# romano16f628.net
KiCad netlist of a schematic drawn in EAGLE
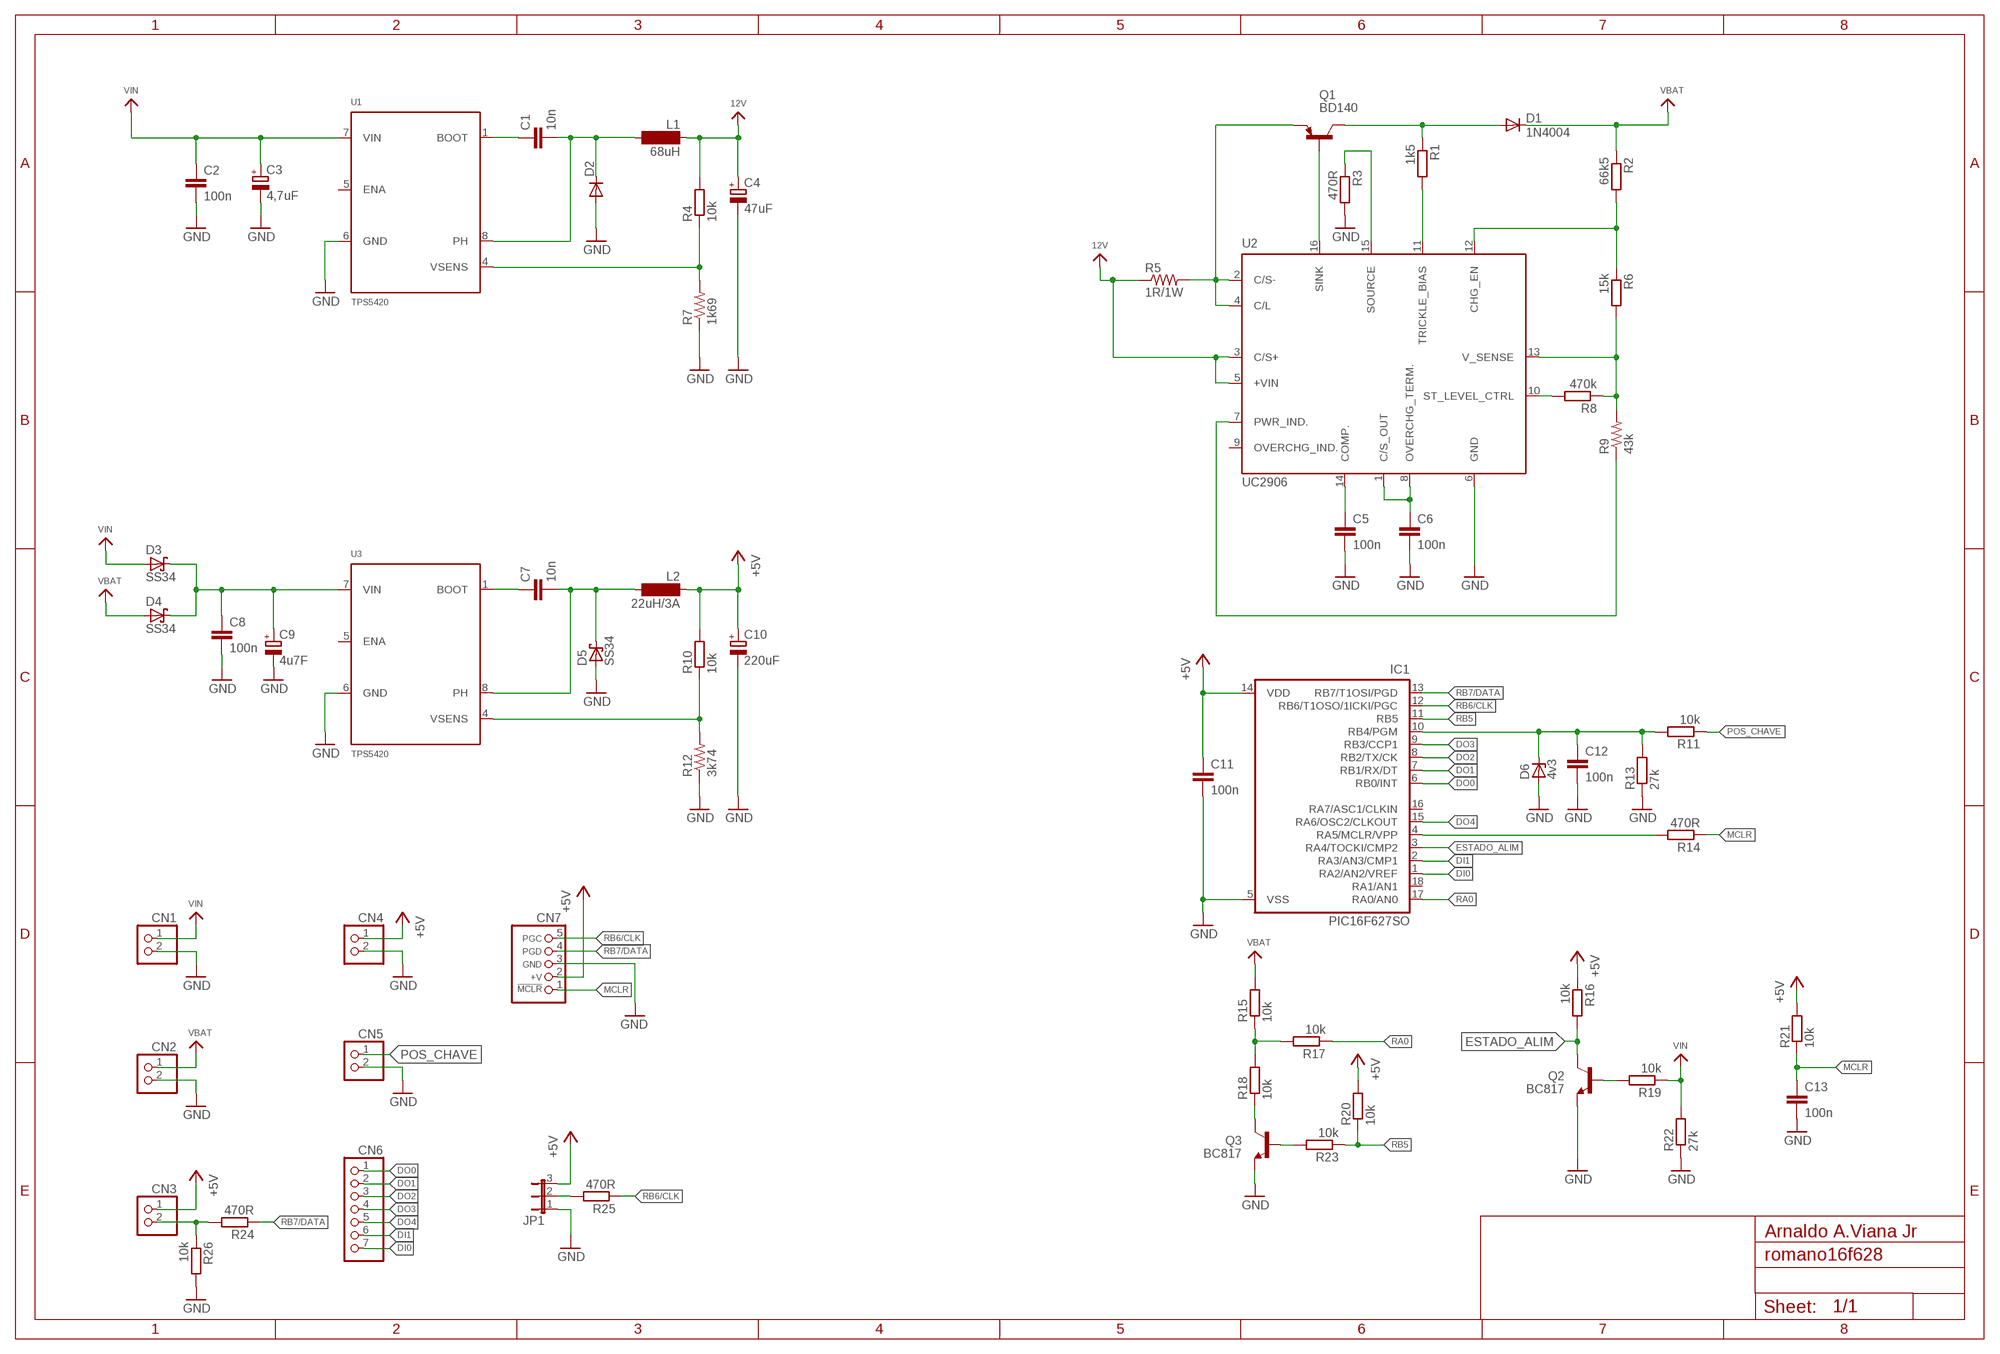
[diagram p0: schematic, sheet 1]

(export (version "E")
  (design (tool "Eeschema 10.0.6"))
  (components
    (comp (ref "C1")
      (value "10n")
      (footprint "eagle-import:C0805")
      (libsource (lib "eagle-import") (part "C-EUC0805"))
    )
    (comp (ref "C2")
      (value "100n")
      (footprint "eagle-import:C0805")
      (libsource (lib "eagle-import") (part "C-EUC0805"))
    )
    (comp (ref "C3")
      (value "4,7uF")
      (footprint "eagle-import:E5-6")
      (libsource (lib "eagle-import") (part "CPOL-EUE5-6"))
    )
    (comp (ref "C4")
      (value "47uF")
      (footprint "eagle-import:E5-6")
      (libsource (lib "eagle-import") (part "CPOL-EUE5-6"))
    )
    (comp (ref "C5")
      (value "100n")
      (footprint "eagle-import:C0805")
      (libsource (lib "eagle-import") (part "C-EUC0805"))
    )
    (comp (ref "C6")
      (value "100n")
      (footprint "eagle-import:C0805")
      (libsource (lib "eagle-import") (part "C-EUC0805"))
    )
    (comp (ref "C7")
      (value "10n")
      (footprint "eagle-import:C0805")
      (libsource (lib "eagle-import") (part "C-EUC0805"))
    )
    (comp (ref "C8")
      (value "100n")
      (footprint "eagle-import:C0805")
      (libsource (lib "eagle-import") (part "C-EUC0805"))
    )
    (comp (ref "C9")
      (value "4u7F")
      (footprint "eagle-import:E5-6")
      (libsource (lib "eagle-import") (part "CPOL-EUE5-6"))
    )
    (comp (ref "C10")
      (value "220uF")
      (footprint "eagle-import:E5-6")
      (libsource (lib "eagle-import") (part "CPOL-EUE5-6"))
    )
    (comp (ref "C11")
      (value "100n")
      (footprint "eagle-import:C0805")
      (libsource (lib "eagle-import") (part "C-EUC0805"))
    )
    (comp (ref "C12")
      (value "100n")
      (footprint "eagle-import:C0805")
      (libsource (lib "eagle-import") (part "C-EUC0805"))
    )
    (comp (ref "C13")
      (value "100n")
      (footprint "eagle-import:C0805")
      (libsource (lib "eagle-import") (part "C-EUC0805"))
    )
    (comp (ref "CN1")
      (value "HEADER-1X2ROUND")
      (footprint "eagle-import:1X02_ROUND")
      (libsource (lib "eagle-import") (part "HEADER-1X2ROUND"))
    )
    (comp (ref "CN2")
      (value "HEADER-1X2ROUND")
      (footprint "eagle-import:1X02_ROUND")
      (libsource (lib "eagle-import") (part "HEADER-1X2ROUND"))
    )
    (comp (ref "CN3")
      (value "HEADER-1X2ROUND")
      (footprint "eagle-import:1X02_ROUND")
      (libsource (lib "eagle-import") (part "HEADER-1X2ROUND"))
    )
    (comp (ref "CN4")
      (value "HEADER-1X2ROUND")
      (footprint "eagle-import:1X02_ROUND")
      (libsource (lib "eagle-import") (part "HEADER-1X2ROUND"))
    )
    (comp (ref "CN5")
      (value "HEADER-1X2ROUND")
      (footprint "eagle-import:1X02_ROUND")
      (libsource (lib "eagle-import") (part "HEADER-1X2ROUND"))
    )
    (comp (ref "CN6")
      (value "HEADER-1X7ROUND")
      (footprint "eagle-import:1X07_ROUND")
      (libsource (lib "eagle-import") (part "HEADER-1X7ROUND"))
    )
    (comp (ref "CN7")
      (value "CON_HEADER_PRG_PIC_ICSP0.1INCH_A")
      (footprint "eagle-import:HEADER_PRG_1X05")
      (libsource (lib "eagle-import") (part "CON_HEADER_PRG_PIC_ICSP0.1INCH_A"))
    )
    (comp (ref "D1")
      (value "1N4004")
      (footprint "eagle-import:DO41-10")
      (libsource (lib "eagle-import") (part "1N4004"))
    )
    (comp (ref "D2")
      (value "DIODE-SOD123")
      (footprint "eagle-import:SOD123")
      (libsource (lib "eagle-import") (part "DIODE-SOD123"))
    )
    (comp (ref "D3")
      (value "SS34")
      (footprint "eagle-import:SMC")
      (libsource (lib "eagle-import") (part "SCHOTTKY-DIODESMC"))
    )
    (comp (ref "D4")
      (value "SS34")
      (footprint "eagle-import:SMC")
      (libsource (lib "eagle-import") (part "SCHOTTKY-DIODESMC"))
    )
    (comp (ref "D5")
      (value "SS34")
      (footprint "eagle-import:SMC")
      (libsource (lib "eagle-import") (part "SCHOTTKY-DIODESMC"))
    )
    (comp (ref "D6")
      (value "4v3")
      (footprint "eagle-import:SOT23")
      (libsource (lib "eagle-import") (part "ZENER-DIODESOT23"))
    )
    (comp (ref "IC1")
      (value "PIC16F627SO")
      (footprint "eagle-import:SO-18W")
      (fields
        (field (name "MF") "MICROCHIP")
        (field (name "MPN") "PIC16F627-04/SO")
        (field (name "MPN_1") "PIC16F627-04/SO")
        (field (name "OC_FARNELL") "1084265")
        (field (name "OC_NEWARK") "69K7632")
      )
      (libsource (lib "eagle-import") (part "PIC16F627SO"))
    )
    (comp (ref "JP1")
      (value "JUMPER3")
      (footprint "eagle-import:JUMPER3")
      (libsource (lib "eagle-import") (part "JUMPER3"))
    )
    (comp (ref "L1")
      (value "68uH")
      (footprint "eagle-import:SD12K100")
      (libsource (lib "eagle-import") (part "SD12K100"))
    )
    (comp (ref "L2")
      (value "22uH/3A")
      (footprint "eagle-import:SD12K100")
      (libsource (lib "eagle-import") (part "SD12K100"))
    )
    (comp (ref "Q1")
      (value "BD140")
      (footprint "eagle-import:TO126")
      (libsource (lib "eagle-import") (part "BD140"))
    )
    (comp (ref "Q2")
      (value "BC817")
      (footprint "eagle-import:SOT23-BEC")
      (libsource (lib "eagle-import") (part "-NPN-SOT23-BECBC817-16"))
    )
    (comp (ref "Q3")
      (value "BC817")
      (footprint "eagle-import:SOT23-BEC")
      (libsource (lib "eagle-import") (part "-NPN-SOT23-BECBC817-16"))
    )
    (comp (ref "R1")
      (value "1k5")
      (footprint "eagle-import:R0805")
      (libsource (lib "eagle-import") (part "R-EU_R0805"))
    )
    (comp (ref "R2")
      (value "66k5")
      (footprint "eagle-import:R0805")
      (libsource (lib "eagle-import") (part "R-EU_R0805"))
    )
    (comp (ref "R3")
      (value "470R")
      (footprint "eagle-import:R0805")
      (libsource (lib "eagle-import") (part "R-EU_R0805"))
    )
    (comp (ref "R4")
      (value "10k")
      (footprint "eagle-import:R0805")
      (libsource (lib "eagle-import") (part "R-EU_R0805"))
    )
    (comp (ref "R5")
      (value "1R/1W")
      (footprint "eagle-import:0805-THM")
      (libsource (lib "eagle-import") (part "RESISTOR_DUAL"))
    )
    (comp (ref "R6")
      (value "15k")
      (footprint "eagle-import:R0805")
      (libsource (lib "eagle-import") (part "R-EU_R0805"))
    )
    (comp (ref "R7")
      (value "1k69")
      (footprint "eagle-import:0805-THM")
      (libsource (lib "eagle-import") (part "RESISTOR_DUAL"))
    )
    (comp (ref "R8")
      (value "470k")
      (footprint "eagle-import:R0805")
      (libsource (lib "eagle-import") (part "R-EU_R0805"))
    )
    (comp (ref "R9")
      (value "43k")
      (footprint "eagle-import:0805-THM")
      (libsource (lib "eagle-import") (part "RESISTOR_DUAL"))
    )
    (comp (ref "R10")
      (value "10k")
      (footprint "eagle-import:R0805")
      (libsource (lib "eagle-import") (part "R-EU_R0805"))
    )
    (comp (ref "R11")
      (value "10k")
      (footprint "eagle-import:R0805")
      (libsource (lib "eagle-import") (part "R-EU_R0805"))
    )
    (comp (ref "R12")
      (value "3k74")
      (footprint "eagle-import:0805-THM")
      (libsource (lib "eagle-import") (part "RESISTOR_DUAL"))
    )
    (comp (ref "R13")
      (value "27k")
      (footprint "eagle-import:R0805")
      (libsource (lib "eagle-import") (part "R-EU_R0805"))
    )
    (comp (ref "R14")
      (value "470R")
      (footprint "eagle-import:R0805")
      (libsource (lib "eagle-import") (part "R-EU_R0805"))
    )
    (comp (ref "R15")
      (value "10k")
      (footprint "eagle-import:R0805")
      (libsource (lib "eagle-import") (part "R-EU_R0805"))
    )
    (comp (ref "R16")
      (value "10k")
      (footprint "eagle-import:R0805")
      (libsource (lib "eagle-import") (part "R-EU_R0805"))
    )
    (comp (ref "R17")
      (value "10k")
      (footprint "eagle-import:R0805")
      (libsource (lib "eagle-import") (part "R-EU_R0805"))
    )
    (comp (ref "R18")
      (value "10k")
      (footprint "eagle-import:R0805")
      (libsource (lib "eagle-import") (part "R-EU_R0805"))
    )
    (comp (ref "R19")
      (value "10k")
      (footprint "eagle-import:R0805")
      (libsource (lib "eagle-import") (part "R-EU_R0805"))
    )
    (comp (ref "R20")
      (value "10k")
      (footprint "eagle-import:R0805")
      (libsource (lib "eagle-import") (part "R-EU_R0805"))
    )
    (comp (ref "R21")
      (value "10k")
      (footprint "eagle-import:R0805")
      (libsource (lib "eagle-import") (part "R-EU_R0805"))
    )
    (comp (ref "R22")
      (value "27k")
      (footprint "eagle-import:R0805")
      (libsource (lib "eagle-import") (part "R-EU_R0805"))
    )
    (comp (ref "R23")
      (value "10k")
      (footprint "eagle-import:R0805")
      (libsource (lib "eagle-import") (part "R-EU_R0805"))
    )
    (comp (ref "R24")
      (value "470R")
      (footprint "eagle-import:R0805")
      (libsource (lib "eagle-import") (part "R-EU_R0805"))
    )
    (comp (ref "R25")
      (value "470R")
      (footprint "eagle-import:R0805")
      (libsource (lib "eagle-import") (part "R-EU_R0805"))
    )
    (comp (ref "R26")
      (value "10k")
      (footprint "eagle-import:R0805")
      (libsource (lib "eagle-import") (part "R-EU_R0805"))
    )
    (comp (ref "U1")
      (value "TPS5420")
      (footprint "eagle-import:SOIC8_150MIL")
      (libsource (lib "eagle-import") (part "TPS5420"))
    )
    (comp (ref "U2")
      (value "UC2906")
      (footprint "eagle-import:SOIC_16")
      (libsource (lib "eagle-import") (part "UC2906"))
    )
    (comp (ref "U3")
      (value "TPS5420")
      (footprint "eagle-import:SOIC8_150MIL")
      (libsource (lib "eagle-import") (part "TPS5420"))
    )
  )
  (nets
    (net (code "1") (name "+5V") (class "Default")
      (node (ref "C10") (pin "+") (pinfunction "+_+") (pintype "passive"))
      (node (ref "C11") (pin "1") (pinfunction "1_1") (pintype "passive"))
      (node (ref "CN3") (pin "1") (pinfunction "1_1") (pintype "passive"))
      (node (ref "CN4") (pin "1") (pinfunction "1_1") (pintype "passive"))
      (node (ref "CN7") (pin "2") (pinfunction "+V_2") (pintype "passive"))
      (node (ref "IC1") (pin "14") (pinfunction "VDD_14") (pintype "power_in"))
      (node (ref "JP1") (pin "3") (pinfunction "3_3") (pintype "passive"))
      (node (ref "L2") (pin "1") (pinfunction "1_1") (pintype "passive"))
      (node (ref "R10") (pin "2") (pinfunction "2_2") (pintype "passive"))
      (node (ref "R16") (pin "1") (pinfunction "1_1") (pintype "passive"))
      (node (ref "R20") (pin "2") (pinfunction "2_2") (pintype "passive"))
      (node (ref "R21") (pin "2") (pinfunction "2_2") (pintype "passive"))
    )
    (net (code "2") (name "12V") (class "Default")
      (node (ref "C4") (pin "+") (pinfunction "+_+") (pintype "passive"))
      (node (ref "L1") (pin "1") (pinfunction "1_1") (pintype "passive"))
      (node (ref "R4") (pin "2") (pinfunction "2_2") (pintype "passive"))
      (node (ref "R5") (pin "1") (pinfunction "1_1") (pintype "passive"))
      (node (ref "U2") (pin "3") (pinfunction "C/S+_3") (pintype "bidirectional"))
      (node (ref "U2") (pin "5") (pinfunction "+VIN_5") (pintype "bidirectional"))
    )
    (net (code "3") (name "DI0") (class "Default")
      (node (ref "CN6") (pin "7") (pinfunction "7_7") (pintype "passive"))
      (node (ref "IC1") (pin "1") (pinfunction "RA2/AN2/VREF_1") (pintype "bidirectional"))
    )
    (net (code "4") (name "DI1") (class "Default")
      (node (ref "CN6") (pin "6") (pinfunction "6_6") (pintype "passive"))
      (node (ref "IC1") (pin "2") (pinfunction "RA3/AN3/CMP1_2") (pintype "bidirectional"))
    )
    (net (code "5") (name "DO0") (class "Default")
      (node (ref "CN6") (pin "1") (pinfunction "1_1") (pintype "passive"))
      (node (ref "IC1") (pin "6") (pinfunction "RB0/INT_6") (pintype "bidirectional"))
    )
    (net (code "6") (name "DO1") (class "Default")
      (node (ref "CN6") (pin "2") (pinfunction "2_2") (pintype "passive"))
      (node (ref "IC1") (pin "7") (pinfunction "RB1/RX/DT_7") (pintype "bidirectional"))
    )
    (net (code "7") (name "DO2") (class "Default")
      (node (ref "CN6") (pin "3") (pinfunction "3_3") (pintype "passive"))
      (node (ref "IC1") (pin "8") (pinfunction "RB2/TX/CK_8") (pintype "bidirectional"))
    )
    (net (code "8") (name "DO3") (class "Default")
      (node (ref "CN6") (pin "4") (pinfunction "4_4") (pintype "passive"))
      (node (ref "IC1") (pin "9") (pinfunction "RB3/CCP1_9") (pintype "bidirectional"))
    )
    (net (code "9") (name "DO4") (class "Default")
      (node (ref "CN6") (pin "5") (pinfunction "5_5") (pintype "passive"))
      (node (ref "IC1") (pin "15") (pinfunction "RA6/OSC2/CLKOUT_15") (pintype "bidirectional"))
    )
    (net (code "10") (name "ESTADO_ALIM") (class "Default")
      (node (ref "IC1") (pin "3") (pinfunction "RA4/TOCKI/CMP2_3") (pintype "bidirectional"))
      (node (ref "Q2") (pin "C") (pinfunction "C_C") (pintype "passive"))
      (node (ref "R16") (pin "2") (pinfunction "2_2") (pintype "passive"))
    )
    (net (code "11") (name "GND") (class "Default")
      (node (ref "C10") (pin "-") (pinfunction "-_-") (pintype "passive"))
      (node (ref "C11") (pin "2") (pinfunction "2_2") (pintype "passive"))
      (node (ref "C12") (pin "2") (pinfunction "2_2") (pintype "passive"))
      (node (ref "C13") (pin "2") (pinfunction "2_2") (pintype "passive"))
      (node (ref "C2") (pin "2") (pinfunction "2_2") (pintype "passive"))
      (node (ref "C3") (pin "-") (pinfunction "-_-") (pintype "passive"))
      (node (ref "C4") (pin "-") (pinfunction "-_-") (pintype "passive"))
      (node (ref "C5") (pin "2") (pinfunction "2_2") (pintype "passive"))
      (node (ref "C6") (pin "2") (pinfunction "2_2") (pintype "passive"))
      (node (ref "C8") (pin "2") (pinfunction "2_2") (pintype "passive"))
      (node (ref "C9") (pin "-") (pinfunction "-_-") (pintype "passive"))
      (node (ref "CN1") (pin "2") (pinfunction "2_2") (pintype "passive"))
      (node (ref "CN2") (pin "2") (pinfunction "2_2") (pintype "passive"))
      (node (ref "CN4") (pin "2") (pinfunction "2_2") (pintype "passive"))
      (node (ref "CN5") (pin "2") (pinfunction "2_2") (pintype "passive"))
      (node (ref "CN7") (pin "3") (pinfunction "GND_3") (pintype "passive"))
      (node (ref "D2") (pin "A") (pinfunction "A_A") (pintype "passive"))
      (node (ref "D5") (pin "A") (pinfunction "A_A") (pintype "passive"))
      (node (ref "D6") (pin "1") (pinfunction "A_1") (pintype "passive"))
      (node (ref "IC1") (pin "5") (pinfunction "VSS_5") (pintype "power_in"))
      (node (ref "JP1") (pin "1") (pinfunction "1_1") (pintype "passive"))
      (node (ref "Q2") (pin "E") (pinfunction "E_E") (pintype "passive"))
      (node (ref "Q3") (pin "E") (pinfunction "E_E") (pintype "passive"))
      (node (ref "R12") (pin "1") (pinfunction "1_1") (pintype "passive"))
      (node (ref "R13") (pin "1") (pinfunction "1_1") (pintype "passive"))
      (node (ref "R22") (pin "1") (pinfunction "1_1") (pintype "passive"))
      (node (ref "R26") (pin "2") (pinfunction "2_2") (pintype "passive"))
      (node (ref "R3") (pin "2") (pinfunction "2_2") (pintype "passive"))
      (node (ref "R7") (pin "1") (pinfunction "1_1") (pintype "passive"))
      (node (ref "U1") (pin "6") (pinfunction "GND_6") (pintype "bidirectional"))
      (node (ref "U2") (pin "6") (pinfunction "GND_6") (pintype "bidirectional"))
      (node (ref "U3") (pin "6") (pinfunction "GND_6") (pintype "bidirectional"))
    )
    (net (code "12") (name "MCLR") (class "Default")
      (node (ref "C13") (pin "1") (pinfunction "1_1") (pintype "passive"))
      (node (ref "CN7") (pin "1") (pinfunction "/MCLR_1") (pintype "passive"))
      (node (ref "R14") (pin "1") (pinfunction "1_1") (pintype "passive"))
      (node (ref "R21") (pin "1") (pinfunction "1_1") (pintype "passive"))
    )
    (net (code "13") (name "Net-(CN3-Pad2)") (class "Default")
      (node (ref "CN3") (pin "2") (pinfunction "2_2") (pintype "passive"))
      (node (ref "R24") (pin "2") (pinfunction "2_2") (pintype "passive"))
      (node (ref "R26") (pin "1") (pinfunction "1_1") (pintype "passive"))
    )
    (net (code "14") (name "Net-(D6-C)") (class "Default")
      (node (ref "C12") (pin "1") (pinfunction "1_1") (pintype "passive"))
      (node (ref "D6") (pin "3") (pinfunction "C_3") (pintype "passive"))
      (node (ref "IC1") (pin "10") (pinfunction "RB4/PGM_10") (pintype "bidirectional"))
      (node (ref "R11") (pin "2") (pinfunction "2_2") (pintype "passive"))
      (node (ref "R13") (pin "2") (pinfunction "2_2") (pintype "passive"))
    )
    (net (code "15") (name "Net-(IC1-RA5{slash}MCLR{slash}VPP)") (class "Default")
      (node (ref "IC1") (pin "4") (pinfunction "RA5/MCLR/VPP_4") (pintype "input"))
      (node (ref "R14") (pin "2") (pinfunction "2_2") (pintype "passive"))
    )
    (net (code "16") (name "Net-(JP1-Pad2)") (class "Default")
      (node (ref "JP1") (pin "2") (pinfunction "2_2") (pintype "passive"))
      (node (ref "R25") (pin "2") (pinfunction "2_2") (pintype "passive"))
    )
    (net (code "17") (name "Net-(Q1-B)") (class "Default")
      (node (ref "Q1") (pin "3") (pinfunction "B_3") (pintype "passive"))
      (node (ref "U2") (pin "16") (pinfunction "SINK_16") (pintype "bidirectional"))
    )
    (net (code "18") (name "Net-(Q1-C)") (class "Default")
      (node (ref "D1") (pin "A") (pinfunction "A_A") (pintype "passive"))
      (node (ref "Q1") (pin "2") (pinfunction "C_2") (pintype "passive"))
      (node (ref "R1") (pin "1") (pinfunction "1_1") (pintype "passive"))
    )
    (net (code "19") (name "Net-(Q1-E)") (class "Default")
      (node (ref "Q1") (pin "1") (pinfunction "E_1") (pintype "passive"))
      (node (ref "R5") (pin "2") (pinfunction "2_2") (pintype "passive"))
      (node (ref "U2") (pin "2") (pinfunction "C/S-_2") (pintype "bidirectional"))
      (node (ref "U2") (pin "4") (pinfunction "C/L_4") (pintype "bidirectional"))
    )
    (net (code "20") (name "Net-(Q2-PadB)") (class "Default")
      (node (ref "Q2") (pin "B") (pinfunction "B_B") (pintype "passive"))
      (node (ref "R19") (pin "2") (pinfunction "2_2") (pintype "passive"))
    )
    (net (code "21") (name "Net-(Q3-PadB)") (class "Default")
      (node (ref "Q3") (pin "B") (pinfunction "B_B") (pintype "passive"))
      (node (ref "R23") (pin "2") (pinfunction "2_2") (pintype "passive"))
    )
    (net (code "22") (name "Net-(Q3-PadC)") (class "Default")
      (node (ref "Q3") (pin "C") (pinfunction "C_C") (pintype "passive"))
      (node (ref "R18") (pin "1") (pinfunction "1_1") (pintype "passive"))
    )
    (net (code "23") (name "Net-(R15-Pad1)") (class "Default")
      (node (ref "R15") (pin "1") (pinfunction "1_1") (pintype "passive"))
      (node (ref "R17") (pin "2") (pinfunction "2_2") (pintype "passive"))
      (node (ref "R18") (pin "2") (pinfunction "2_2") (pintype "passive"))
    )
    (net (code "24") (name "Net-(U1-BOOT)") (class "Default")
      (node (ref "C1") (pin "1") (pinfunction "1_1") (pintype "passive"))
      (node (ref "U1") (pin "1") (pinfunction "BOOT_1") (pintype "bidirectional"))
    )
    (net (code "25") (name "Net-(U1-PH)") (class "Default")
      (node (ref "C1") (pin "2") (pinfunction "2_2") (pintype "passive"))
      (node (ref "D2") (pin "C") (pinfunction "C_C") (pintype "passive"))
      (node (ref "L1") (pin "2") (pinfunction "2_2") (pintype "passive"))
      (node (ref "U1") (pin "8") (pinfunction "PH_8") (pintype "bidirectional"))
    )
    (net (code "26") (name "Net-(U1-VSENS)") (class "Default")
      (node (ref "R4") (pin "1") (pinfunction "1_1") (pintype "passive"))
      (node (ref "R7") (pin "2") (pinfunction "2_2") (pintype "passive"))
      (node (ref "U1") (pin "4") (pinfunction "VSENS_4") (pintype "bidirectional"))
    )
    (net (code "27") (name "Net-(U2-CHG_EN)") (class "Default")
      (node (ref "R2") (pin "2") (pinfunction "2_2") (pintype "passive"))
      (node (ref "R6") (pin "1") (pinfunction "1_1") (pintype "passive"))
      (node (ref "U2") (pin "12") (pinfunction "CHG_EN_12") (pintype "bidirectional"))
    )
    (net (code "28") (name "Net-(U2-COMP.)") (class "Default")
      (node (ref "C5") (pin "1") (pinfunction "1_1") (pintype "passive"))
      (node (ref "U2") (pin "14") (pinfunction "COMP._14") (pintype "bidirectional"))
    )
    (net (code "29") (name "Net-(U2-C{slash}S_OUT)") (class "Default")
      (node (ref "C6") (pin "1") (pinfunction "1_1") (pintype "passive"))
      (node (ref "U2") (pin "1") (pinfunction "C/S_OUT_1") (pintype "bidirectional"))
      (node (ref "U2") (pin "8") (pinfunction "OVERCHG_TERM._8") (pintype "bidirectional"))
    )
    (net (code "30") (name "Net-(U2-PWR_IND.)") (class "Default")
      (node (ref "R9") (pin "1") (pinfunction "1_1") (pintype "passive"))
      (node (ref "U2") (pin "7") (pinfunction "PWR_IND._7") (pintype "bidirectional"))
    )
    (net (code "31") (name "Net-(U2-SOURCE)") (class "Default")
      (node (ref "R3") (pin "1") (pinfunction "1_1") (pintype "passive"))
      (node (ref "U2") (pin "15") (pinfunction "SOURCE_15") (pintype "bidirectional"))
    )
    (net (code "32") (name "Net-(U2-ST_LEVEL_CTRL)") (class "Default")
      (node (ref "R8") (pin "2") (pinfunction "2_2") (pintype "passive"))
      (node (ref "U2") (pin "10") (pinfunction "ST_LEVEL_CTRL_10") (pintype "bidirectional"))
    )
    (net (code "33") (name "Net-(U2-TRICKLE_BIAS)") (class "Default")
      (node (ref "R1") (pin "2") (pinfunction "2_2") (pintype "passive"))
      (node (ref "U2") (pin "11") (pinfunction "TRICKLE_BIAS_11") (pintype "bidirectional"))
    )
    (net (code "34") (name "Net-(U2-V_SENSE)") (class "Default")
      (node (ref "R6") (pin "2") (pinfunction "2_2") (pintype "passive"))
      (node (ref "R8") (pin "1") (pinfunction "1_1") (pintype "passive"))
      (node (ref "R9") (pin "2") (pinfunction "2_2") (pintype "passive"))
      (node (ref "U2") (pin "13") (pinfunction "V_SENSE_13") (pintype "bidirectional"))
    )
    (net (code "35") (name "Net-(U3-BOOT)") (class "Default")
      (node (ref "C7") (pin "1") (pinfunction "1_1") (pintype "passive"))
      (node (ref "U3") (pin "1") (pinfunction "BOOT_1") (pintype "bidirectional"))
    )
    (net (code "36") (name "Net-(U3-PH)") (class "Default")
      (node (ref "C7") (pin "2") (pinfunction "2_2") (pintype "passive"))
      (node (ref "D5") (pin "C") (pinfunction "C_C") (pintype "passive"))
      (node (ref "L2") (pin "2") (pinfunction "2_2") (pintype "passive"))
      (node (ref "U3") (pin "8") (pinfunction "PH_8") (pintype "bidirectional"))
    )
    (net (code "37") (name "Net-(U3-VIN)") (class "Default")
      (node (ref "C8") (pin "1") (pinfunction "1_1") (pintype "passive"))
      (node (ref "C9") (pin "+") (pinfunction "+_+") (pintype "passive"))
      (node (ref "D3") (pin "C") (pinfunction "C_C") (pintype "passive"))
      (node (ref "D4") (pin "C") (pinfunction "C_C") (pintype "passive"))
      (node (ref "U3") (pin "7") (pinfunction "VIN_7") (pintype "bidirectional"))
    )
    (net (code "38") (name "Net-(U3-VSENS)") (class "Default")
      (node (ref "R10") (pin "1") (pinfunction "1_1") (pintype "passive"))
      (node (ref "R12") (pin "2") (pinfunction "2_2") (pintype "passive"))
      (node (ref "U3") (pin "4") (pinfunction "VSENS_4") (pintype "bidirectional"))
    )
    (net (code "39") (name "POS_CHAVE") (class "Default")
      (node (ref "CN5") (pin "1") (pinfunction "1_1") (pintype "passive"))
      (node (ref "R11") (pin "1") (pinfunction "1_1") (pintype "passive"))
    )
    (net (code "40") (name "RA0") (class "Default")
      (node (ref "IC1") (pin "17") (pinfunction "RA0/AN0_17") (pintype "bidirectional"))
      (node (ref "R17") (pin "1") (pinfunction "1_1") (pintype "passive"))
    )
    (net (code "41") (name "RB5") (class "Default")
      (node (ref "IC1") (pin "11") (pinfunction "RB5_11") (pintype "bidirectional"))
      (node (ref "R20") (pin "1") (pinfunction "1_1") (pintype "passive"))
      (node (ref "R23") (pin "1") (pinfunction "1_1") (pintype "passive"))
    )
    (net (code "42") (name "RB6{slash}CLK") (class "Default")
      (node (ref "CN7") (pin "5") (pinfunction "PGC_5") (pintype "passive"))
      (node (ref "IC1") (pin "12") (pinfunction "RB6/T1OSO/1ICKI/PGC_12") (pintype "bidirectional"))
      (node (ref "R25") (pin "1") (pinfunction "1_1") (pintype "passive"))
    )
    (net (code "43") (name "RB7{slash}DATA") (class "Default")
      (node (ref "CN7") (pin "4") (pinfunction "PGD_4") (pintype "passive"))
      (node (ref "IC1") (pin "13") (pinfunction "RB7/T1OSI/PGD_13") (pintype "bidirectional"))
      (node (ref "R24") (pin "1") (pinfunction "1_1") (pintype "passive"))
    )
    (net (code "44") (name "VBAT") (class "Default")
      (node (ref "CN2") (pin "1") (pinfunction "1_1") (pintype "passive"))
      (node (ref "D1") (pin "C") (pinfunction "C_C") (pintype "passive"))
      (node (ref "D4") (pin "A") (pinfunction "A_A") (pintype "passive"))
      (node (ref "R15") (pin "2") (pinfunction "2_2") (pintype "passive"))
      (node (ref "R2") (pin "1") (pinfunction "1_1") (pintype "passive"))
    )
    (net (code "45") (name "VIN") (class "Default")
      (node (ref "C2") (pin "1") (pinfunction "1_1") (pintype "passive"))
      (node (ref "C3") (pin "+") (pinfunction "+_+") (pintype "passive"))
      (node (ref "CN1") (pin "1") (pinfunction "1_1") (pintype "passive"))
      (node (ref "D3") (pin "A") (pinfunction "A_A") (pintype "passive"))
      (node (ref "R19") (pin "1") (pinfunction "1_1") (pintype "passive"))
      (node (ref "R22") (pin "2") (pinfunction "2_2") (pintype "passive"))
      (node (ref "U1") (pin "7") (pinfunction "VIN_7") (pintype "bidirectional"))
    )
    (net (code "46") (name "unconnected-(IC1-RA1{slash}AN1-Pad18)") (class "Default")
      (node (ref "IC1") (pin "18") (pinfunction "RA1/AN1_18") (pintype "bidirectional"))
    )
    (net (code "47") (name "unconnected-(IC1-RA7{slash}ASC1{slash}CLKIN-Pad16)") (class "Default")
      (node (ref "IC1") (pin "16") (pinfunction "RA7/ASC1/CLKIN_16") (pintype "bidirectional"))
    )
    (net (code "48") (name "unconnected-(U1-ENA-Pad5)") (class "Default")
      (node (ref "U1") (pin "5") (pinfunction "ENA_5") (pintype "bidirectional"))
    )
    (net (code "49") (name "unconnected-(U2-OVERCHG_IND.-Pad9)") (class "Default")
      (node (ref "U2") (pin "9") (pinfunction "OVERCHG_IND._9") (pintype "bidirectional"))
    )
    (net (code "50") (name "unconnected-(U3-ENA-Pad5)") (class "Default")
      (node (ref "U3") (pin "5") (pinfunction "ENA_5") (pintype "bidirectional"))
    )
  )
)
